# cell_connector.net
KiCad netlist of a schematic drawn in Altium Designer
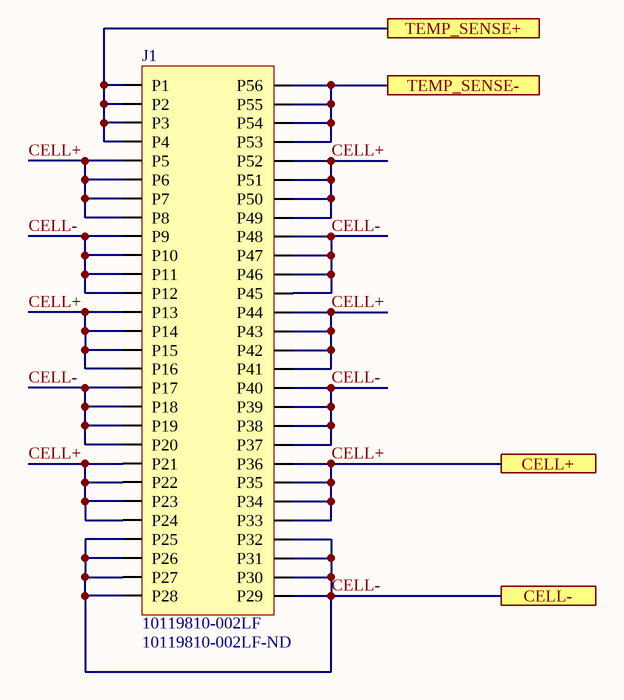
[diagram p0: cell_connector.SchDoc]

(export (version "E")
  (design (tool "Eeschema 10.0.6"))
  (components
    (comp (ref "J1")
      (value "10119810-002LF")
      (footprint "10119810-002LF - Connector")
      (description "56 Position Female Connector Non Specified - Dual Edge Gold or Gold, GXT™  Black")
      (fields
        (field (name "MANUFACTURER") "Amphenol ICC (FCI)")
        (field (name "SUPPLIER PART NUMBER 1") "10119810-002LF-ND")
      )
      (libsource (lib "bms") (part "10119810-002LF - Connector"))
    )
  )
  (nets
    (net (code "1") (name "/CELL+") (class "Default")
      (node (ref "J1") (pin "P13") (pinfunction "P13_P13") (pintype "power_in"))
      (node (ref "J1") (pin "P14") (pinfunction "P14_P14") (pintype "power_in"))
      (node (ref "J1") (pin "P15") (pinfunction "P15_P15") (pintype "power_in"))
      (node (ref "J1") (pin "P16") (pinfunction "P16_P16") (pintype "power_in"))
      (node (ref "J1") (pin "P21") (pinfunction "P21_P21") (pintype "power_in"))
      (node (ref "J1") (pin "P22") (pinfunction "P22_P22") (pintype "power_in"))
      (node (ref "J1") (pin "P23") (pinfunction "P23_P23") (pintype "power_in"))
      (node (ref "J1") (pin "P24") (pinfunction "P24_P24") (pintype "power_in"))
      (node (ref "J1") (pin "P33") (pinfunction "P33_P33") (pintype "power_in"))
      (node (ref "J1") (pin "P34") (pinfunction "P34_P34") (pintype "power_in"))
      (node (ref "J1") (pin "P35") (pinfunction "P35_P35") (pintype "power_in"))
      (node (ref "J1") (pin "P36") (pinfunction "P36_P36") (pintype "power_in"))
      (node (ref "J1") (pin "P41") (pinfunction "P41_P41") (pintype "power_in"))
      (node (ref "J1") (pin "P42") (pinfunction "P42_P42") (pintype "power_in"))
      (node (ref "J1") (pin "P43") (pinfunction "P43_P43") (pintype "power_in"))
      (node (ref "J1") (pin "P44") (pinfunction "P44_P44") (pintype "power_in"))
      (node (ref "J1") (pin "P49") (pinfunction "P49_P49") (pintype "power_in"))
      (node (ref "J1") (pin "P5") (pinfunction "P5_P5") (pintype "power_in"))
      (node (ref "J1") (pin "P50") (pinfunction "P50_P50") (pintype "power_in"))
      (node (ref "J1") (pin "P51") (pinfunction "P51_P51") (pintype "power_in"))
      (node (ref "J1") (pin "P52") (pinfunction "P52_P52") (pintype "power_in"))
      (node (ref "J1") (pin "P6") (pinfunction "P6_P6") (pintype "power_in"))
      (node (ref "J1") (pin "P7") (pinfunction "P7_P7") (pintype "power_in"))
      (node (ref "J1") (pin "P8") (pinfunction "P8_P8") (pintype "power_in"))
    )
    (net (code "2") (name "/CELL-") (class "Default")
      (node (ref "J1") (pin "P10") (pinfunction "P10_P10") (pintype "power_in"))
      (node (ref "J1") (pin "P11") (pinfunction "P11_P11") (pintype "power_in"))
      (node (ref "J1") (pin "P12") (pinfunction "P12_P12") (pintype "power_in"))
      (node (ref "J1") (pin "P17") (pinfunction "P17_P17") (pintype "power_in"))
      (node (ref "J1") (pin "P18") (pinfunction "P18_P18") (pintype "power_in"))
      (node (ref "J1") (pin "P19") (pinfunction "P19_P19") (pintype "power_in"))
      (node (ref "J1") (pin "P20") (pinfunction "P20_P20") (pintype "power_in"))
      (node (ref "J1") (pin "P25") (pinfunction "P25_P25") (pintype "power_in"))
      (node (ref "J1") (pin "P26") (pinfunction "P26_P26") (pintype "power_in"))
      (node (ref "J1") (pin "P27") (pinfunction "P27_P27") (pintype "power_in"))
      (node (ref "J1") (pin "P28") (pinfunction "P28_P28") (pintype "power_in"))
      (node (ref "J1") (pin "P29") (pinfunction "P29_P29") (pintype "power_in"))
      (node (ref "J1") (pin "P30") (pinfunction "P30_P30") (pintype "power_in"))
      (node (ref "J1") (pin "P31") (pinfunction "P31_P31") (pintype "power_in"))
      (node (ref "J1") (pin "P32") (pinfunction "P32_P32") (pintype "power_in"))
      (node (ref "J1") (pin "P37") (pinfunction "P37_P37") (pintype "power_in"))
      (node (ref "J1") (pin "P38") (pinfunction "P38_P38") (pintype "power_in"))
      (node (ref "J1") (pin "P39") (pinfunction "P39_P39") (pintype "power_in"))
      (node (ref "J1") (pin "P40") (pinfunction "P40_P40") (pintype "power_in"))
      (node (ref "J1") (pin "P45") (pinfunction "P45_P45") (pintype "power_in"))
      (node (ref "J1") (pin "P46") (pinfunction "P46_P46") (pintype "power_in"))
      (node (ref "J1") (pin "P47") (pinfunction "P47_P47") (pintype "power_in"))
      (node (ref "J1") (pin "P48") (pinfunction "P48_P48") (pintype "power_in"))
      (node (ref "J1") (pin "P9") (pinfunction "P9_P9") (pintype "power_in"))
    )
    (net (code "3") (name "/TEMP_SENSE+") (class "Default")
      (node (ref "J1") (pin "P1") (pinfunction "P1_P1") (pintype "power_in"))
      (node (ref "J1") (pin "P2") (pinfunction "P2_P2") (pintype "power_in"))
      (node (ref "J1") (pin "P3") (pinfunction "P3_P3") (pintype "power_in"))
      (node (ref "J1") (pin "P4") (pinfunction "P4_P4") (pintype "power_in"))
    )
    (net (code "4") (name "/TEMP_SENSE-") (class "Default")
      (node (ref "J1") (pin "P53") (pinfunction "P53_P53") (pintype "power_in"))
      (node (ref "J1") (pin "P54") (pinfunction "P54_P54") (pintype "power_in"))
      (node (ref "J1") (pin "P55") (pinfunction "P55_P55") (pintype "power_in"))
      (node (ref "J1") (pin "P56") (pinfunction "P56_P56") (pintype "power_in"))
    )
  )
)
